# StepperDriverBoard.net
KiCad netlist of a schematic drawn in EAGLE
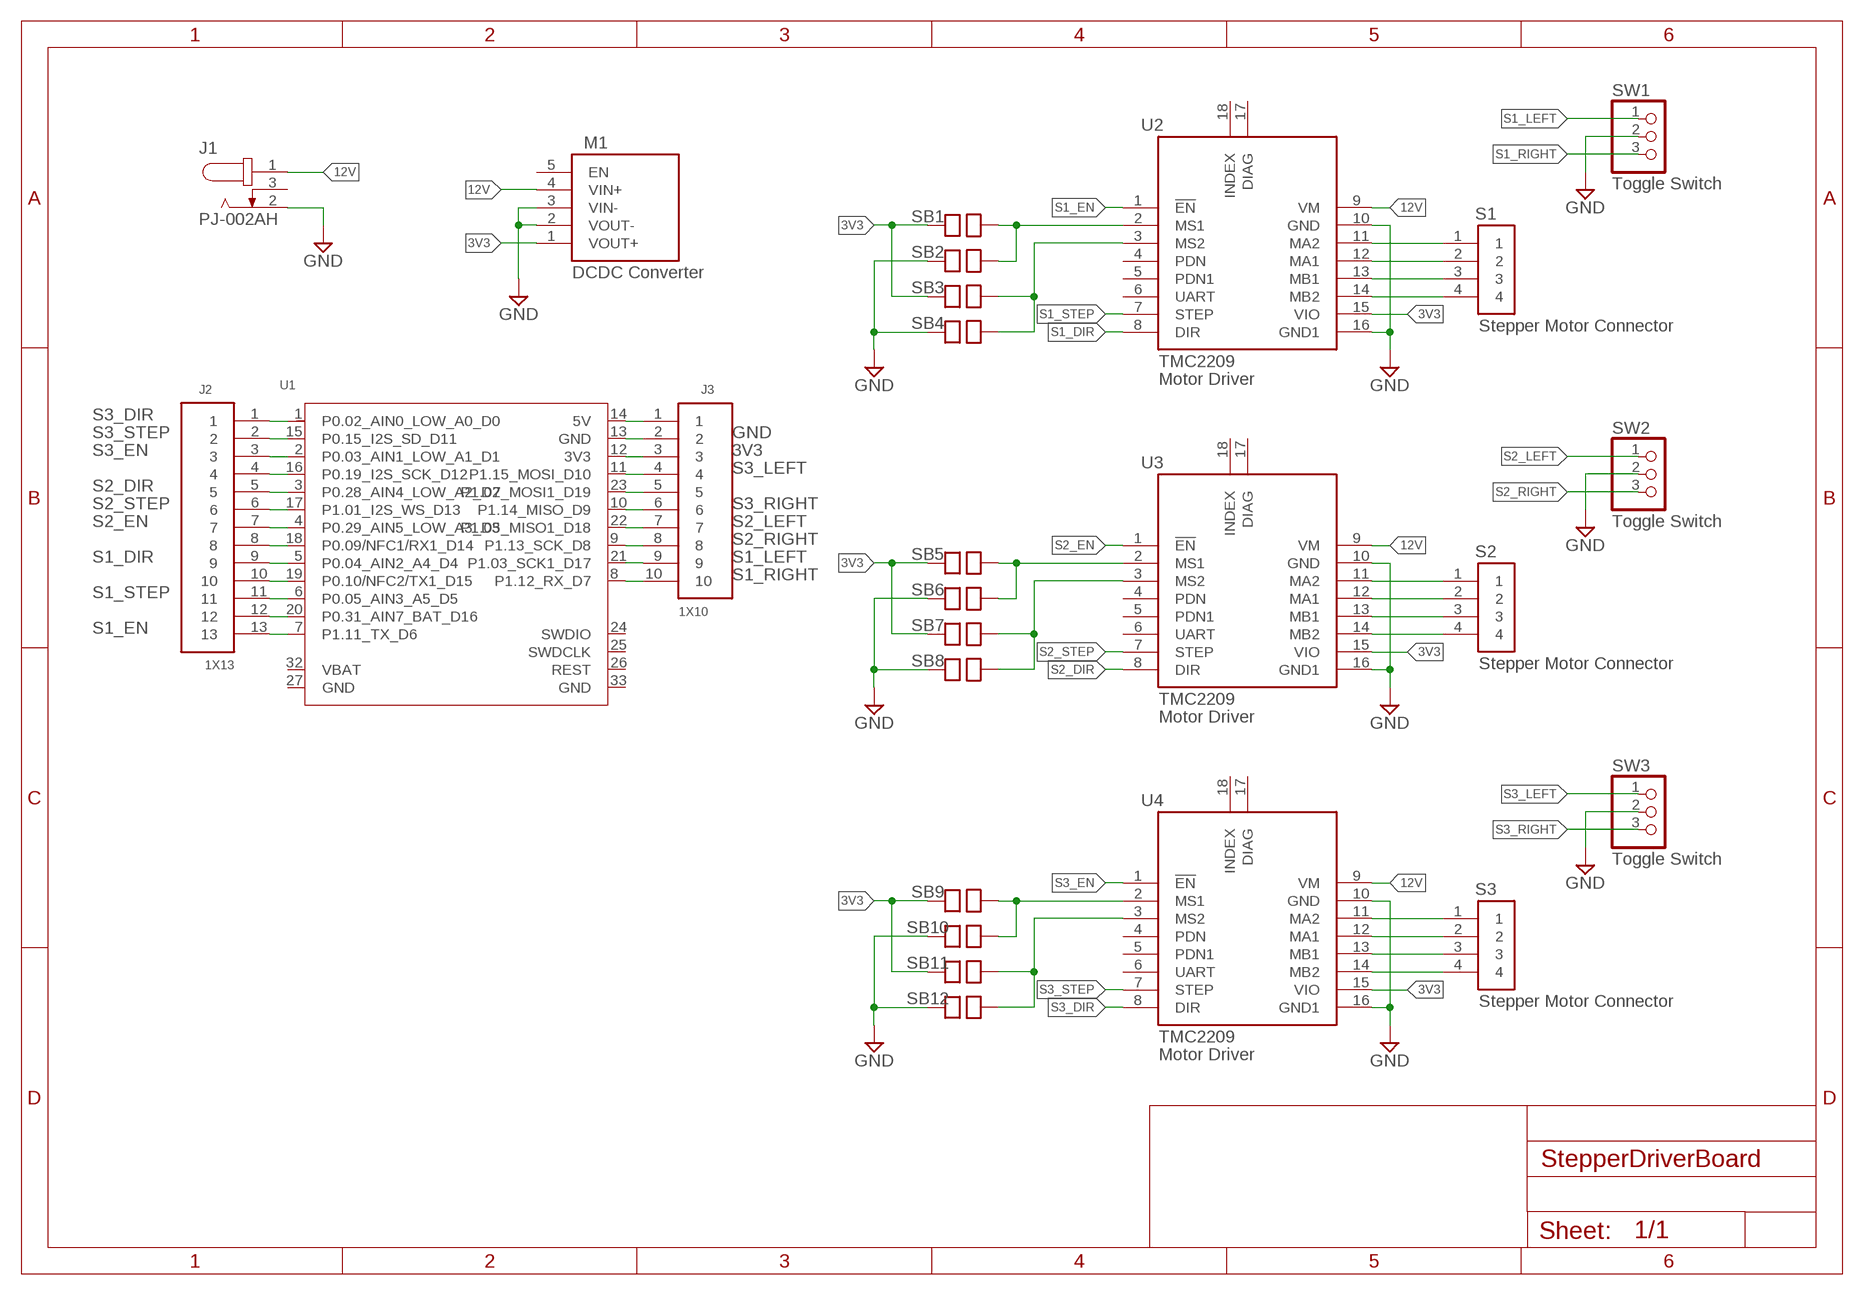
[diagram p0: schematic, sheet 1]

(export (version "E")
  (design (tool "Eeschema 10.0.6"))
  (components
    (comp (ref "J1")
      (value "PJ-002AH")
      (footprint "eagle-import:CUI_PJ-002AH")
      (fields (field (name "DIGIKEY_PART_NUMBER") "CP-002AH-ND") (field (name "MF") "Same Sky"))
      (libsource (lib "eagle-import") (part "PJ-002AH"))
    )
    (comp (ref "J2")
      (value "1X13")
      (footprint "eagle-import:1X13-127MM")
      (libsource (lib "eagle-import") (part "1X13"))
    )
    (comp (ref "J3")
      (value "1X10")
      (footprint "eagle-import:1X10-127MM")
      (libsource (lib "eagle-import") (part "1X10"))
    )
    (comp (ref "M1")
      (value "DCDC Converter")
      (footprint "eagle-import:DROK_5V")
      (libsource (lib "eagle-import") (part "DROK_5V"))
    )
    (comp (ref "S1")
      (value "Stepper Motor Connector")
      (footprint "eagle-import:1X04-BIG")
      (libsource (lib "eagle-import") (part "1X4-BIG"))
    )
    (comp (ref "S2")
      (value "Stepper Motor Connector")
      (footprint "eagle-import:1X04-BIG")
      (libsource (lib "eagle-import") (part "1X4-BIG"))
    )
    (comp (ref "S3")
      (value "Stepper Motor Connector")
      (footprint "eagle-import:1X04-BIG")
      (libsource (lib "eagle-import") (part "1X4-BIG"))
    )
    (comp (ref "SB1")
      (value "JUMPERP")
      (footprint "eagle-import:JUMPER")
      (libsource (lib "eagle-import") (part "JUMPERP"))
    )
    (comp (ref "SB2")
      (value "JUMPERP")
      (footprint "eagle-import:JUMPER")
      (libsource (lib "eagle-import") (part "JUMPERP"))
    )
    (comp (ref "SB3")
      (value "JUMPERP")
      (footprint "eagle-import:JUMPER")
      (libsource (lib "eagle-import") (part "JUMPERP"))
    )
    (comp (ref "SB4")
      (value "JUMPERP")
      (footprint "eagle-import:JUMPER")
      (libsource (lib "eagle-import") (part "JUMPERP"))
    )
    (comp (ref "SB5")
      (value "JUMPERP")
      (footprint "eagle-import:JUMPER")
      (libsource (lib "eagle-import") (part "JUMPERP"))
    )
    (comp (ref "SB6")
      (value "JUMPERP")
      (footprint "eagle-import:JUMPER")
      (libsource (lib "eagle-import") (part "JUMPERP"))
    )
    (comp (ref "SB7")
      (value "JUMPERP")
      (footprint "eagle-import:JUMPER")
      (libsource (lib "eagle-import") (part "JUMPERP"))
    )
    (comp (ref "SB8")
      (value "JUMPERP")
      (footprint "eagle-import:JUMPER")
      (libsource (lib "eagle-import") (part "JUMPERP"))
    )
    (comp (ref "SB9")
      (value "JUMPERP")
      (footprint "eagle-import:JUMPER")
      (libsource (lib "eagle-import") (part "JUMPERP"))
    )
    (comp (ref "SB10")
      (value "JUMPERP")
      (footprint "eagle-import:JUMPER")
      (libsource (lib "eagle-import") (part "JUMPERP"))
    )
    (comp (ref "SB11")
      (value "JUMPERP")
      (footprint "eagle-import:JUMPER")
      (libsource (lib "eagle-import") (part "JUMPERP"))
    )
    (comp (ref "SB12")
      (value "JUMPERP")
      (footprint "eagle-import:JUMPER")
      (libsource (lib "eagle-import") (part "JUMPERP"))
    )
    (comp (ref "SW1")
      (value "Toggle Switch")
      (footprint "eagle-import:1X03")
      (fields (field (name "MANUFACTURER") "Generic"))
      (libsource (lib "eagle-import") (part "PINHD-1X3"))
    )
    (comp (ref "SW2")
      (value "Toggle Switch")
      (footprint "eagle-import:1X03")
      (fields (field (name "MANUFACTURER") "Generic"))
      (libsource (lib "eagle-import") (part "PINHD-1X3"))
    )
    (comp (ref "SW3")
      (value "Toggle Switch")
      (footprint "eagle-import:1X03")
      (fields (field (name "MANUFACTURER") "Generic"))
      (libsource (lib "eagle-import") (part "PINHD-1X3"))
    )
    (comp (ref "U1")
      (value "XIAO-NRF52840_PLUS_SMDXIAO-NRF52840_PLUS")
      (footprint "eagle-import:XIAO-NRF52840_PLUS_SMD")
      (libsource (lib "eagle-import") (part "XIAO-NRF52840_PLUS_SMDXIAO-NRF52840_PLUS"))
    )
    (comp (ref "U2")
      (value "TMC2209")
      (footprint "eagle-import:MODULE_TMC2209_PINS")
      (libsource (lib "eagle-import") (part "TMC2209_PINS"))
    )
    (comp (ref "U3")
      (value "TMC2209")
      (footprint "eagle-import:MODULE_TMC2209_PINS")
      (libsource (lib "eagle-import") (part "TMC2209_PINS"))
    )
    (comp (ref "U4")
      (value "TMC2209")
      (footprint "eagle-import:MODULE_TMC2209_PINS")
      (libsource (lib "eagle-import") (part "TMC2209_PINS"))
    )
  )
  (nets
    (net (code "1") (name "3V3") (class "Default")
      (node (ref "J3") (pin "3") (pinfunction "3_3") (pintype "bidirectional"))
      (node (ref "M1") (pin "1") (pinfunction "VOUT+_1") (pintype "bidirectional"))
      (node (ref "SB1") (pin "1") (pinfunction "1_1") (pintype "passive"))
      (node (ref "SB11") (pin "1") (pinfunction "1_1") (pintype "passive"))
      (node (ref "SB3") (pin "1") (pinfunction "1_1") (pintype "passive"))
      (node (ref "SB5") (pin "1") (pinfunction "1_1") (pintype "passive"))
      (node (ref "SB7") (pin "1") (pinfunction "1_1") (pintype "passive"))
      (node (ref "SB9") (pin "1") (pinfunction "1_1") (pintype "passive"))
      (node (ref "U1") (pin "12") (pinfunction "3V3_12") (pintype "passive"))
      (node (ref "U2") (pin "15") (pinfunction "VIO_15") (pintype "power_in"))
      (node (ref "U3") (pin "15") (pinfunction "VIO_15") (pintype "power_in"))
      (node (ref "U4") (pin "15") (pinfunction "VIO_15") (pintype "power_in"))
    )
    (net (code "2") (name "12V") (class "Default")
      (node (ref "J1") (pin "1") (pinfunction "1_1") (pintype "passive"))
      (node (ref "M1") (pin "4") (pinfunction "VIN+_4") (pintype "bidirectional"))
      (node (ref "U2") (pin "9") (pinfunction "VM_9") (pintype "power_in"))
      (node (ref "U3") (pin "9") (pinfunction "VM_9") (pintype "power_in"))
      (node (ref "U4") (pin "9") (pinfunction "VM_9") (pintype "power_in"))
    )
    (net (code "3") (name "GND") (class "Default")
      (node (ref "J1") (pin "2") (pinfunction "2_2") (pintype "passive"))
      (node (ref "J3") (pin "2") (pinfunction "2_2") (pintype "bidirectional"))
      (node (ref "M1") (pin "2") (pinfunction "VOUT-_2") (pintype "bidirectional"))
      (node (ref "M1") (pin "3") (pinfunction "VIN-_3") (pintype "bidirectional"))
      (node (ref "SB10") (pin "1") (pinfunction "1_1") (pintype "passive"))
      (node (ref "SB12") (pin "1") (pinfunction "1_1") (pintype "passive"))
      (node (ref "SB2") (pin "1") (pinfunction "1_1") (pintype "passive"))
      (node (ref "SB4") (pin "1") (pinfunction "1_1") (pintype "passive"))
      (node (ref "SB6") (pin "1") (pinfunction "1_1") (pintype "passive"))
      (node (ref "SB8") (pin "1") (pinfunction "1_1") (pintype "passive"))
      (node (ref "SW1") (pin "2") (pinfunction "2_2") (pintype "passive"))
      (node (ref "SW2") (pin "2") (pinfunction "2_2") (pintype "passive"))
      (node (ref "SW3") (pin "2") (pinfunction "2_2") (pintype "passive"))
      (node (ref "U1") (pin "13") (pinfunction "GND_13") (pintype "passive"))
      (node (ref "U2") (pin "10") (pinfunction "GND_10") (pintype "input"))
      (node (ref "U2") (pin "16") (pinfunction "GND1_16") (pintype "power_in"))
      (node (ref "U3") (pin "10") (pinfunction "GND_10") (pintype "input"))
      (node (ref "U3") (pin "16") (pinfunction "GND1_16") (pintype "power_in"))
      (node (ref "U4") (pin "10") (pinfunction "GND_10") (pintype "input"))
      (node (ref "U4") (pin "16") (pinfunction "GND1_16") (pintype "power_in"))
    )
    (net (code "4") (name "Net-(U1-5V)") (class "Default")
      (node (ref "J3") (pin "1") (pinfunction "1_1") (pintype "bidirectional"))
      (node (ref "U1") (pin "14") (pinfunction "5V_14") (pintype "passive"))
    )
    (net (code "5") (name "Net-(U1-P0.09{slash}NFC1{slash}RX1_D14)") (class "Default")
      (node (ref "J2") (pin "8") (pinfunction "8_8") (pintype "bidirectional"))
      (node (ref "U1") (pin "18") (pinfunction "P0.09/NFC1/RX1_D14_18") (pintype "passive"))
    )
    (net (code "6") (name "Net-(U1-P0.10{slash}NFC2{slash}TX1_D15)") (class "Default")
      (node (ref "J2") (pin "10") (pinfunction "10_10") (pintype "bidirectional"))
      (node (ref "U1") (pin "19") (pinfunction "P0.10/NFC2/TX1_D15_19") (pintype "passive"))
    )
    (net (code "7") (name "Net-(U1-P0.19_I2S_SCK_D12)") (class "Default")
      (node (ref "J2") (pin "4") (pinfunction "4_4") (pintype "bidirectional"))
      (node (ref "U1") (pin "16") (pinfunction "P0.19_I2S_SCK_D12_16") (pintype "passive"))
    )
    (net (code "8") (name "Net-(U1-P0.31_AIN7_BAT_D16)") (class "Default")
      (node (ref "J2") (pin "12") (pinfunction "12_12") (pintype "bidirectional"))
      (node (ref "U1") (pin "20") (pinfunction "P0.31_AIN7_BAT_D16_20") (pintype "passive"))
    )
    (net (code "9") (name "Net-(U1-P1.07_MOSI1_D19)") (class "Default")
      (node (ref "J3") (pin "5") (pinfunction "5_5") (pintype "bidirectional"))
      (node (ref "U1") (pin "23") (pinfunction "P1.07_MOSI1_D19_23") (pintype "passive"))
    )
    (net (code "10") (name "Net-(U2-MA1)") (class "Default")
      (node (ref "S1") (pin "2") (pinfunction "2_2") (pintype "bidirectional"))
      (node (ref "U2") (pin "12") (pinfunction "MA1_12") (pintype "output"))
    )
    (net (code "11") (name "Net-(U2-MA2)") (class "Default")
      (node (ref "S1") (pin "1") (pinfunction "1_1") (pintype "bidirectional"))
      (node (ref "U2") (pin "11") (pinfunction "MA2_11") (pintype "output"))
    )
    (net (code "12") (name "Net-(U2-MB1)") (class "Default")
      (node (ref "S1") (pin "3") (pinfunction "3_3") (pintype "bidirectional"))
      (node (ref "U2") (pin "13") (pinfunction "MB1_13") (pintype "output"))
    )
    (net (code "13") (name "Net-(U2-MB2)") (class "Default")
      (node (ref "S1") (pin "4") (pinfunction "4_4") (pintype "bidirectional"))
      (node (ref "U2") (pin "14") (pinfunction "MB2_14") (pintype "output"))
    )
    (net (code "14") (name "Net-(U2-MS1)") (class "Default")
      (node (ref "SB1") (pin "2") (pinfunction "2_2") (pintype "passive"))
      (node (ref "SB2") (pin "2") (pinfunction "2_2") (pintype "passive"))
      (node (ref "U2") (pin "2") (pinfunction "MS1_2") (pintype "input"))
    )
    (net (code "15") (name "Net-(U2-MS2)") (class "Default")
      (node (ref "SB3") (pin "2") (pinfunction "2_2") (pintype "passive"))
      (node (ref "SB4") (pin "2") (pinfunction "2_2") (pintype "passive"))
      (node (ref "U2") (pin "3") (pinfunction "MS2_3") (pintype "input"))
    )
    (net (code "16") (name "Net-(U3-MA1)") (class "Default")
      (node (ref "S2") (pin "2") (pinfunction "2_2") (pintype "bidirectional"))
      (node (ref "U3") (pin "12") (pinfunction "MA1_12") (pintype "output"))
    )
    (net (code "17") (name "Net-(U3-MA2)") (class "Default")
      (node (ref "S2") (pin "1") (pinfunction "1_1") (pintype "bidirectional"))
      (node (ref "U3") (pin "11") (pinfunction "MA2_11") (pintype "output"))
    )
    (net (code "18") (name "Net-(U3-MB1)") (class "Default")
      (node (ref "S2") (pin "3") (pinfunction "3_3") (pintype "bidirectional"))
      (node (ref "U3") (pin "13") (pinfunction "MB1_13") (pintype "output"))
    )
    (net (code "19") (name "Net-(U3-MB2)") (class "Default")
      (node (ref "S2") (pin "4") (pinfunction "4_4") (pintype "bidirectional"))
      (node (ref "U3") (pin "14") (pinfunction "MB2_14") (pintype "output"))
    )
    (net (code "20") (name "Net-(U3-MS1)") (class "Default")
      (node (ref "SB5") (pin "2") (pinfunction "2_2") (pintype "passive"))
      (node (ref "SB6") (pin "2") (pinfunction "2_2") (pintype "passive"))
      (node (ref "U3") (pin "2") (pinfunction "MS1_2") (pintype "input"))
    )
    (net (code "21") (name "Net-(U3-MS2)") (class "Default")
      (node (ref "SB7") (pin "2") (pinfunction "2_2") (pintype "passive"))
      (node (ref "SB8") (pin "2") (pinfunction "2_2") (pintype "passive"))
      (node (ref "U3") (pin "3") (pinfunction "MS2_3") (pintype "input"))
    )
    (net (code "22") (name "Net-(U4-MA1)") (class "Default")
      (node (ref "S3") (pin "2") (pinfunction "2_2") (pintype "bidirectional"))
      (node (ref "U4") (pin "12") (pinfunction "MA1_12") (pintype "output"))
    )
    (net (code "23") (name "Net-(U4-MA2)") (class "Default")
      (node (ref "S3") (pin "1") (pinfunction "1_1") (pintype "bidirectional"))
      (node (ref "U4") (pin "11") (pinfunction "MA2_11") (pintype "output"))
    )
    (net (code "24") (name "Net-(U4-MB1)") (class "Default")
      (node (ref "S3") (pin "3") (pinfunction "3_3") (pintype "bidirectional"))
      (node (ref "U4") (pin "13") (pinfunction "MB1_13") (pintype "output"))
    )
    (net (code "25") (name "Net-(U4-MB2)") (class "Default")
      (node (ref "S3") (pin "4") (pinfunction "4_4") (pintype "bidirectional"))
      (node (ref "U4") (pin "14") (pinfunction "MB2_14") (pintype "output"))
    )
    (net (code "26") (name "Net-(U4-MS1)") (class "Default")
      (node (ref "SB10") (pin "2") (pinfunction "2_2") (pintype "passive"))
      (node (ref "SB9") (pin "2") (pinfunction "2_2") (pintype "passive"))
      (node (ref "U4") (pin "2") (pinfunction "MS1_2") (pintype "input"))
    )
    (net (code "27") (name "Net-(U4-MS2)") (class "Default")
      (node (ref "SB11") (pin "2") (pinfunction "2_2") (pintype "passive"))
      (node (ref "SB12") (pin "2") (pinfunction "2_2") (pintype "passive"))
      (node (ref "U4") (pin "3") (pinfunction "MS2_3") (pintype "input"))
    )
    (net (code "28") (name "S1_DIR") (class "Default")
      (node (ref "J2") (pin "9") (pinfunction "9_9") (pintype "bidirectional"))
      (node (ref "U1") (pin "5") (pinfunction "P0.04_AIN2_A4_D4_5") (pintype "passive"))
      (node (ref "U2") (pin "8") (pinfunction "DIR_8") (pintype "input"))
    )
    (net (code "29") (name "S1_EN") (class "Default")
      (node (ref "J2") (pin "13") (pinfunction "13_13") (pintype "bidirectional"))
      (node (ref "U1") (pin "7") (pinfunction "P1.11_TX_D6_7") (pintype "passive"))
      (node (ref "U2") (pin "1") (pinfunction "~{EN}_1") (pintype "input"))
    )
    (net (code "30") (name "S1_LEFT") (class "Default")
      (node (ref "J3") (pin "9") (pinfunction "9_9") (pintype "bidirectional"))
      (node (ref "SW1") (pin "1") (pinfunction "1_1") (pintype "passive"))
      (node (ref "U1") (pin "21") (pinfunction "P1.03_SCK1_D17_21") (pintype "passive"))
    )
    (net (code "31") (name "S1_RIGHT") (class "Default")
      (node (ref "J3") (pin "10") (pinfunction "10_10") (pintype "bidirectional"))
      (node (ref "SW1") (pin "3") (pinfunction "3_3") (pintype "passive"))
      (node (ref "U1") (pin "8") (pinfunction "P1.12_RX_D7_8") (pintype "passive"))
    )
    (net (code "32") (name "S1_STEP") (class "Default")
      (node (ref "J2") (pin "11") (pinfunction "11_11") (pintype "bidirectional"))
      (node (ref "U1") (pin "6") (pinfunction "P0.05_AIN3_A5_D5_6") (pintype "passive"))
      (node (ref "U2") (pin "7") (pinfunction "STEP_7") (pintype "input"))
    )
    (net (code "33") (name "S2_DIR") (class "Default")
      (node (ref "J2") (pin "5") (pinfunction "5_5") (pintype "bidirectional"))
      (node (ref "U1") (pin "3") (pinfunction "P0.28_AIN4_LOW_A2_D2_3") (pintype "passive"))
      (node (ref "U3") (pin "8") (pinfunction "DIR_8") (pintype "input"))
    )
    (net (code "34") (name "S2_EN") (class "Default")
      (node (ref "J2") (pin "7") (pinfunction "7_7") (pintype "bidirectional"))
      (node (ref "U1") (pin "4") (pinfunction "P0.29_AIN5_LOW_A3_D3_4") (pintype "passive"))
      (node (ref "U3") (pin "1") (pinfunction "~{EN}_1") (pintype "input"))
    )
    (net (code "35") (name "S2_LEFT") (class "Default")
      (node (ref "J3") (pin "7") (pinfunction "7_7") (pintype "bidirectional"))
      (node (ref "SW2") (pin "1") (pinfunction "1_1") (pintype "passive"))
      (node (ref "U1") (pin "22") (pinfunction "P1.05_MISO1_D18_22") (pintype "passive"))
    )
    (net (code "36") (name "S2_RIGHT") (class "Default")
      (node (ref "J3") (pin "8") (pinfunction "8_8") (pintype "bidirectional"))
      (node (ref "SW2") (pin "3") (pinfunction "3_3") (pintype "passive"))
      (node (ref "U1") (pin "9") (pinfunction "P1.13_SCK_D8_9") (pintype "passive"))
    )
    (net (code "37") (name "S2_STEP") (class "Default")
      (node (ref "J2") (pin "6") (pinfunction "6_6") (pintype "bidirectional"))
      (node (ref "U1") (pin "17") (pinfunction "P1.01_I2S_WS_D13_17") (pintype "passive"))
      (node (ref "U3") (pin "7") (pinfunction "STEP_7") (pintype "input"))
    )
    (net (code "38") (name "S3_DIR") (class "Default")
      (node (ref "J2") (pin "1") (pinfunction "1_1") (pintype "bidirectional"))
      (node (ref "U1") (pin "1") (pinfunction "P0.02_AIN0_LOW_A0_D0_1") (pintype "passive"))
      (node (ref "U4") (pin "8") (pinfunction "DIR_8") (pintype "input"))
    )
    (net (code "39") (name "S3_EN") (class "Default")
      (node (ref "J2") (pin "3") (pinfunction "3_3") (pintype "bidirectional"))
      (node (ref "U1") (pin "2") (pinfunction "P0.03_AIN1_LOW_A1_D1_2") (pintype "passive"))
      (node (ref "U4") (pin "1") (pinfunction "~{EN}_1") (pintype "input"))
    )
    (net (code "40") (name "S3_LEFT") (class "Default")
      (node (ref "J3") (pin "4") (pinfunction "4_4") (pintype "bidirectional"))
      (node (ref "SW3") (pin "1") (pinfunction "1_1") (pintype "passive"))
      (node (ref "U1") (pin "11") (pinfunction "P1.15_MOSI_D10_11") (pintype "passive"))
    )
    (net (code "41") (name "S3_RIGHT") (class "Default")
      (node (ref "J3") (pin "6") (pinfunction "6_6") (pintype "bidirectional"))
      (node (ref "SW3") (pin "3") (pinfunction "3_3") (pintype "passive"))
      (node (ref "U1") (pin "10") (pinfunction "P1.14_MISO_D9_10") (pintype "passive"))
    )
    (net (code "42") (name "S3_STEP") (class "Default")
      (node (ref "J2") (pin "2") (pinfunction "2_2") (pintype "bidirectional"))
      (node (ref "U1") (pin "15") (pinfunction "P0.15_I2S_SD_D11_15") (pintype "passive"))
      (node (ref "U4") (pin "7") (pinfunction "STEP_7") (pintype "input"))
    )
    (net (code "43") (name "unconnected-(J1-Pad3)") (class "Default")
      (node (ref "J1") (pin "3") (pinfunction "3_3") (pintype "passive"))
    )
    (net (code "44") (name "unconnected-(M1-EN-Pad5)") (class "Default")
      (node (ref "M1") (pin "5") (pinfunction "EN_5") (pintype "bidirectional"))
    )
    (net (code "45") (name "unconnected-(U1-GND-Pad27)") (class "Default")
      (node (ref "U1") (pin "27") (pinfunction "GND_27") (pintype "passive"))
    )
    (net (code "46") (name "unconnected-(U1-GND-Pad33)") (class "Default")
      (node (ref "U1") (pin "33") (pinfunction "GND_33") (pintype "passive"))
    )
    (net (code "47") (name "unconnected-(U1-REST-Pad26)") (class "Default")
      (node (ref "U1") (pin "26") (pinfunction "REST_26") (pintype "passive"))
    )
    (net (code "48") (name "unconnected-(U1-SWDCLK-Pad25)") (class "Default")
      (node (ref "U1") (pin "25") (pinfunction "SWDCLK_25") (pintype "passive"))
    )
    (net (code "49") (name "unconnected-(U1-SWDIO-Pad24)") (class "Default")
      (node (ref "U1") (pin "24") (pinfunction "SWDIO_24") (pintype "passive"))
    )
    (net (code "50") (name "unconnected-(U1-VBAT-Pad32)") (class "Default")
      (node (ref "U1") (pin "32") (pinfunction "VBAT_32") (pintype "passive"))
    )
    (net (code "51") (name "unconnected-(U2-DIAG-Pad17)") (class "Default")
      (node (ref "U2") (pin "17") (pinfunction "DIAG_17") (pintype "output"))
    )
    (net (code "52") (name "unconnected-(U2-INDEX-Pad18)") (class "Default")
      (node (ref "U2") (pin "18") (pinfunction "INDEX_18") (pintype "output"))
    )
    (net (code "53") (name "unconnected-(U2-PDN-Pad4)") (class "Default")
      (node (ref "U2") (pin "4") (pinfunction "PDN_4") (pintype "bidirectional"))
    )
    (net (code "54") (name "unconnected-(U2-PDN1-Pad5)") (class "Default")
      (node (ref "U2") (pin "5") (pinfunction "PDN1_5") (pintype "bidirectional"))
    )
    (net (code "55") (name "unconnected-(U2-UART-Pad6)") (class "Default")
      (node (ref "U2") (pin "6") (pinfunction "UART_6") (pintype "bidirectional"))
    )
    (net (code "56") (name "unconnected-(U3-DIAG-Pad17)") (class "Default")
      (node (ref "U3") (pin "17") (pinfunction "DIAG_17") (pintype "output"))
    )
    (net (code "57") (name "unconnected-(U3-INDEX-Pad18)") (class "Default")
      (node (ref "U3") (pin "18") (pinfunction "INDEX_18") (pintype "output"))
    )
    (net (code "58") (name "unconnected-(U3-PDN-Pad4)") (class "Default")
      (node (ref "U3") (pin "4") (pinfunction "PDN_4") (pintype "bidirectional"))
    )
    (net (code "59") (name "unconnected-(U3-PDN1-Pad5)") (class "Default")
      (node (ref "U3") (pin "5") (pinfunction "PDN1_5") (pintype "bidirectional"))
    )
    (net (code "60") (name "unconnected-(U3-UART-Pad6)") (class "Default")
      (node (ref "U3") (pin "6") (pinfunction "UART_6") (pintype "bidirectional"))
    )
    (net (code "61") (name "unconnected-(U4-DIAG-Pad17)") (class "Default")
      (node (ref "U4") (pin "17") (pinfunction "DIAG_17") (pintype "output"))
    )
    (net (code "62") (name "unconnected-(U4-INDEX-Pad18)") (class "Default")
      (node (ref "U4") (pin "18") (pinfunction "INDEX_18") (pintype "output"))
    )
    (net (code "63") (name "unconnected-(U4-PDN-Pad4)") (class "Default")
      (node (ref "U4") (pin "4") (pinfunction "PDN_4") (pintype "bidirectional"))
    )
    (net (code "64") (name "unconnected-(U4-PDN1-Pad5)") (class "Default")
      (node (ref "U4") (pin "5") (pinfunction "PDN1_5") (pintype "bidirectional"))
    )
    (net (code "65") (name "unconnected-(U4-UART-Pad6)") (class "Default")
      (node (ref "U4") (pin "6") (pinfunction "UART_6") (pintype "bidirectional"))
    )
  )
)
